# Adc_I2C.net
KiCad netlist of a schematic drawn in Altium Designer
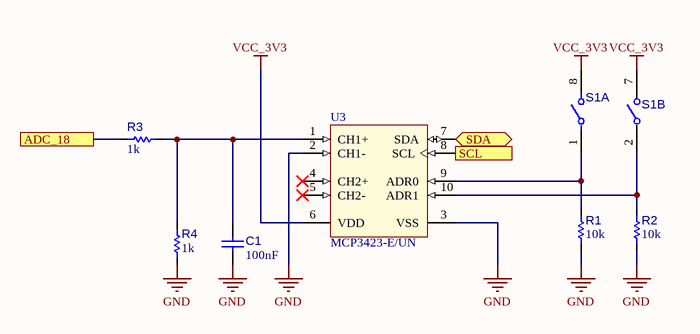
[diagram p0: Adc_I2C.SchDoc]

(export (version "E")
  (design (tool "Eeschema 10.0.6"))
  (components
    (comp (ref "C1")
      (value "100nF")
      (footprint "C_1608[0603]")
      (description "Capacitor type 1")
      (fields (field (name "TOLERANCE") "10%") (field (name "Comment") "CAP CER 100nF 50V 0603"))
      (libsource (lib "TEP-AltiumLib-Passives-RLC") (part "capacitor"))
    )
    (comp (ref "R1")
      (value "10k")
      (footprint "R_1608[0603]")
      (description "Resistor type 1")
      (fields (field (name "TOLERANCE") "1%") (field (name "Comment") "Res 10k 1% 0603"))
      (libsource (lib "TEP-AltiumLib-Passives-RLC") (part "resistor"))
    )
    (comp (ref "R2")
      (value "10k")
      (footprint "R_1608[0603]")
      (description "Resistor type 1")
      (fields (field (name "TOLERANCE") "1%") (field (name "Comment") "Res 10k 1% 0603"))
      (libsource (lib "TEP-AltiumLib-Passives-RLC") (part "resistor"))
    )
    (comp (ref "R3")
      (value "1k")
      (footprint "R_1608[0603]")
      (description "Resistor type 1")
      (fields (field (name "TOLERANCE") "1%") (field (name "Comment") "Res 1k 1% 0603"))
      (libsource (lib "TEP-AltiumLib-Passives-RLC") (part "resistor"))
    )
    (comp (ref "R4")
      (value "1k")
      (footprint "R_1608[0603]")
      (description "Resistor type 1")
      (fields (field (name "TOLERANCE") "1%") (field (name "Comment") "Res 1k 1% 0603"))
      (libsource (lib "TEP-AltiumLib-Passives-RLC") (part "resistor"))
    )
    (comp (ref "S1")
      (value "DSHP04TSGER")
      (footprint "S_DIP_SWITCH_50MIL_4POS")
      (description "SWITCH DIP SLIDE SPST 25MA 24V, pitch 1.27mm, height 1.55mm")
      (libsource (lib "TEP-AltiumLib") (part "SW_DIP_50MIL_4POS"))
    )
    (comp (ref "U3")
      (value "MCP3423-E/UN")
      (footprint "U_MSOP50P300X500-10(RM-10)_WO-TP")
      (description "CAN Controller Stand-Alone With SPI, 18-Pin PDIP")
      (libsource (lib "TEP-AltiumLib-ICs") (part "U_MCP3423-E/UN"))
    )
  )
  (nets
    (net (code "1") (name "/ADC_18") (class "Default")
      (node (ref "R3") (pin "1") (pinfunction "1_1") (pintype "passive"))
    )
    (net (code "2") (name "/SCL") (class "Default")
      (node (ref "U3") (pin "8") (pinfunction "SCL_8") (pintype "input"))
    )
    (net (code "3") (name "/SDA") (class "Default")
      (node (ref "U3") (pin "7") (pinfunction "SDA_7") (pintype "bidirectional"))
    )
    (net (code "4") (name "GND") (class "Default")
      (node (ref "C1") (pin "1") (pinfunction "1_1") (pintype "passive"))
      (node (ref "R1") (pin "1") (pinfunction "1_1") (pintype "passive"))
      (node (ref "R2") (pin "1") (pinfunction "1_1") (pintype "passive"))
      (node (ref "R4") (pin "1") (pinfunction "1_1") (pintype "passive"))
      (node (ref "U3") (pin "2") (pinfunction "CH1-_2") (pintype "input"))
      (node (ref "U3") (pin "3") (pinfunction "VSS_3") (pintype "power_in"))
    )
    (net (code "5") (name "Net-(U3-ADR0)") (class "Default")
      (node (ref "R1") (pin "2") (pinfunction "2_2") (pintype "passive"))
      (node (ref "S1") (pin "1") (pinfunction "1_1") (pintype "passive"))
      (node (ref "U3") (pin "9") (pinfunction "ADR0_9") (pintype "input"))
    )
    (net (code "6") (name "Net-(U3-ADR1)") (class "Default")
      (node (ref "R2") (pin "2") (pinfunction "2_2") (pintype "passive"))
      (node (ref "S1") (pin "2") (pinfunction "2_2") (pintype "passive"))
      (node (ref "U3") (pin "10") (pinfunction "ADR1_10") (pintype "input"))
    )
    (net (code "7") (name "Net-(U3-CH1+)") (class "Default")
      (node (ref "C1") (pin "2") (pinfunction "2_2") (pintype "passive"))
      (node (ref "R3") (pin "2") (pinfunction "2_2") (pintype "passive"))
      (node (ref "R4") (pin "2") (pinfunction "2_2") (pintype "passive"))
      (node (ref "U3") (pin "1") (pinfunction "CH1+_1") (pintype "input"))
    )
    (net (code "8") (name "VCC_3V3") (class "Default")
      (node (ref "S1") (pin "7") (pinfunction "7_7") (pintype "passive"))
      (node (ref "S1") (pin "8") (pinfunction "8_8") (pintype "passive"))
      (node (ref "U3") (pin "6") (pinfunction "VDD_6") (pintype "power_in"))
    )
    (net (code "9") (name "unconnected-(U3-CH2+-Pad4)") (class "Default")
      (node (ref "U3") (pin "4") (pinfunction "CH2+_4") (pintype "input+no_connect"))
    )
    (net (code "10") (name "unconnected-(U3-CH2--Pad5)") (class "Default")
      (node (ref "U3") (pin "5") (pinfunction "CH2-_5") (pintype "input+no_connect"))
    )
  )
)
